# tile.net
KiCad netlist of a schematic drawn in EAGLE
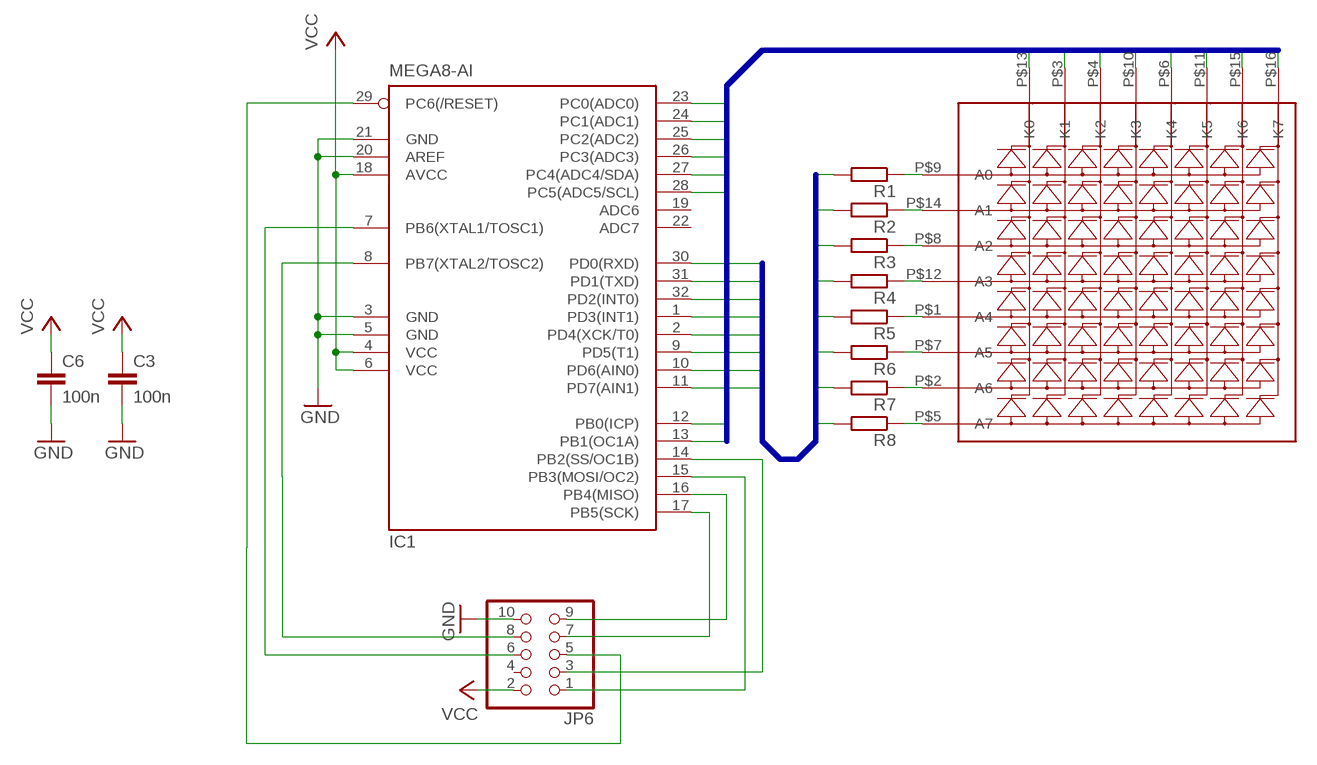
[diagram p0: schematic, sheet 1]
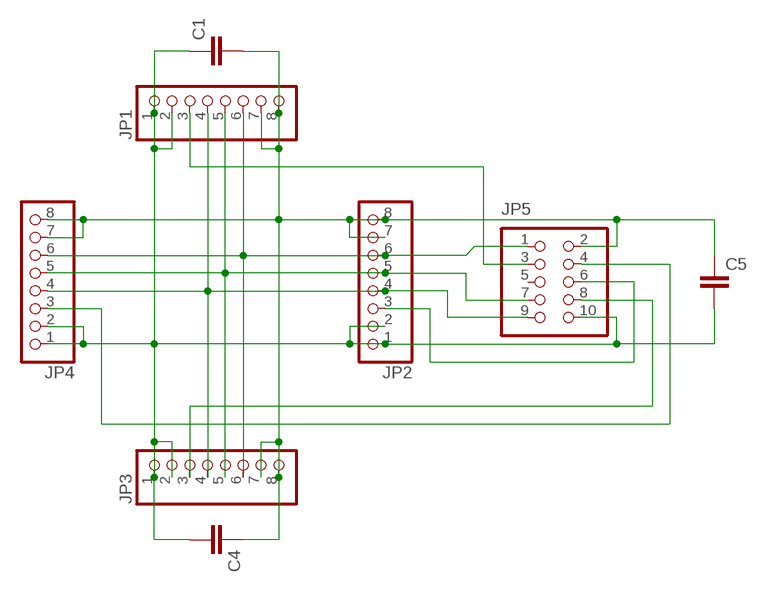
[diagram p1: schematic, sheet 2]

(export (version "E")
  (design (tool "Eeschema 10.0.6"))
  (components
    (comp (ref "C1")
      (value "C-EUC0805")
      (footprint "eagle-import:C0805")
      (libsource (lib "eagle-import") (part "C-EUC0805"))
    )
    (comp (ref "C4")
      (value "C-EUC0805")
      (footprint "eagle-import:C0805")
      (libsource (lib "eagle-import") (part "C-EUC0805"))
    )
    (comp (ref "C5")
      (value "C-EUC0805")
      (footprint "eagle-import:C0805")
      (libsource (lib "eagle-import") (part "C-EUC0805"))
    )
    (comp (ref "JP1")
      (value "PINHD-1X8_2.00")
      (footprint "eagle-import:1X08M")
      (libsource (lib "eagle-import") (part "PINHD-1X8_2.00"))
    )
    (comp (ref "JP2")
      (value "PINHD-1X8_2.00")
      (footprint "eagle-import:1X08M")
      (libsource (lib "eagle-import") (part "PINHD-1X8_2.00"))
    )
    (comp (ref "JP3")
      (value "PINHD-1X8_2.00")
      (footprint "eagle-import:1X08M")
      (libsource (lib "eagle-import") (part "PINHD-1X8_2.00"))
    )
    (comp (ref "JP4")
      (value "PINHD-1X8_2.00")
      (footprint "eagle-import:1X08M")
      (libsource (lib "eagle-import") (part "PINHD-1X8_2.00"))
    )
    (comp (ref "JP5")
      (value "PINHD-2X5_2.54")
      (footprint "eagle-import:2X05")
      (libsource (lib "eagle-import") (part "PINHD-2X5_2.54"))
    )
    (comp (ref "C3")
      (value "100n")
      (footprint "eagle-import:C0805")
      (libsource (lib "eagle-import") (part "C-EUC0805"))
    )
    (comp (ref "C6")
      (value "100n")
      (footprint "eagle-import:C0805")
      (libsource (lib "eagle-import") (part "C-EUC0805"))
    )
    (comp (ref "IC1")
      (value "MEGA8-AI")
      (footprint "eagle-import:TQFP32-08")
      (libsource (lib "eagle-import") (part "MEGA8-AI"))
    )
    (comp (ref "JP6")
      (value "PINHD-2X5_2.54")
      (footprint "eagle-import:2X05")
      (libsource (lib "eagle-import") (part "PINHD-2X5_2.54"))
    )
    (comp (ref "R1")
      (value "R-EU_M0805")
      (footprint "eagle-import:M0805")
      (libsource (lib "eagle-import") (part "R-EU_M0805"))
    )
    (comp (ref "R2")
      (value "R-EU_M0805")
      (footprint "eagle-import:M0805")
      (libsource (lib "eagle-import") (part "R-EU_M0805"))
    )
    (comp (ref "R3")
      (value "R-EU_M0805")
      (footprint "eagle-import:M0805")
      (libsource (lib "eagle-import") (part "R-EU_M0805"))
    )
    (comp (ref "R4")
      (value "R-EU_M0805")
      (footprint "eagle-import:M0805")
      (libsource (lib "eagle-import") (part "R-EU_M0805"))
    )
    (comp (ref "R5")
      (value "R-EU_M0805")
      (footprint "eagle-import:M0805")
      (libsource (lib "eagle-import") (part "R-EU_M0805"))
    )
    (comp (ref "R6")
      (value "R-EU_M0805")
      (footprint "eagle-import:M0805")
      (libsource (lib "eagle-import") (part "R-EU_M0805"))
    )
    (comp (ref "R7")
      (value "R-EU_M0805")
      (footprint "eagle-import:M0805")
      (libsource (lib "eagle-import") (part "R-EU_M0805"))
    )
    (comp (ref "R8")
      (value "R-EU_M0805")
      (footprint "eagle-import:M0805")
      (libsource (lib "eagle-import") (part "R-EU_M0805"))
    )
    (comp (ref "U$1")
      (value "LED-MATRIX")
      (footprint "eagle-import:LED-MATRIX")
      (libsource (lib "eagle-import") (part "LED-MATRIX"))
    )
  )
  (nets
    (net (code "1") (name "A0") (class "Default")
      (node (ref "IC1") (pin "30") (pinfunction "PD0(RXD)_30") (pintype "bidirectional"))
      (node (ref "R1") (pin "1") (pinfunction "1_1") (pintype "passive"))
      (node (ref "R1") (pin "2") (pinfunction "2_2") (pintype "passive"))
      (node (ref "U$1") (pin "P$9") (pinfunction "A0_P$9") (pintype "bidirectional"))
    )
    (net (code "2") (name "A1") (class "Default")
      (node (ref "IC1") (pin "31") (pinfunction "PD1(TXD)_31") (pintype "bidirectional"))
      (node (ref "R2") (pin "1") (pinfunction "1_1") (pintype "passive"))
      (node (ref "R2") (pin "2") (pinfunction "2_2") (pintype "passive"))
      (node (ref "U$1") (pin "P$14") (pinfunction "A1_P$14") (pintype "bidirectional"))
    )
    (net (code "3") (name "A2") (class "Default")
      (node (ref "IC1") (pin "32") (pinfunction "PD2(INT0)_32") (pintype "bidirectional"))
      (node (ref "R3") (pin "1") (pinfunction "1_1") (pintype "passive"))
      (node (ref "R3") (pin "2") (pinfunction "2_2") (pintype "passive"))
      (node (ref "U$1") (pin "P$8") (pinfunction "A2_P$8") (pintype "bidirectional"))
    )
    (net (code "4") (name "A3") (class "Default")
      (node (ref "IC1") (pin "1") (pinfunction "PD3(INT1)_1") (pintype "bidirectional"))
      (node (ref "R4") (pin "1") (pinfunction "1_1") (pintype "passive"))
      (node (ref "R4") (pin "2") (pinfunction "2_2") (pintype "passive"))
      (node (ref "U$1") (pin "P$12") (pinfunction "A3_P$12") (pintype "bidirectional"))
    )
    (net (code "5") (name "A4") (class "Default")
      (node (ref "IC1") (pin "2") (pinfunction "PD4(XCK/T0)_2") (pintype "bidirectional"))
      (node (ref "R5") (pin "1") (pinfunction "1_1") (pintype "passive"))
      (node (ref "U$1") (pin "P$1") (pinfunction "A4_P$1") (pintype "bidirectional"))
    )
    (net (code "6") (name "A5") (class "Default")
      (node (ref "IC1") (pin "9") (pinfunction "PD5(T1)_9") (pintype "bidirectional"))
      (node (ref "R5") (pin "2") (pinfunction "2_2") (pintype "passive"))
      (node (ref "R6") (pin "1") (pinfunction "1_1") (pintype "passive"))
      (node (ref "R6") (pin "2") (pinfunction "2_2") (pintype "passive"))
      (node (ref "U$1") (pin "P$7") (pinfunction "A5_P$7") (pintype "bidirectional"))
    )
    (net (code "7") (name "A6") (class "Default")
      (node (ref "IC1") (pin "10") (pinfunction "PD6(AIN0)_10") (pintype "bidirectional"))
      (node (ref "R7") (pin "1") (pinfunction "1_1") (pintype "passive"))
      (node (ref "R7") (pin "2") (pinfunction "2_2") (pintype "passive"))
      (node (ref "U$1") (pin "P$2") (pinfunction "A6_P$2") (pintype "bidirectional"))
    )
    (net (code "8") (name "A7") (class "Default")
      (node (ref "IC1") (pin "11") (pinfunction "PD7(AIN1)_11") (pintype "bidirectional"))
      (node (ref "R8") (pin "1") (pinfunction "1_1") (pintype "passive"))
      (node (ref "R8") (pin "2") (pinfunction "2_2") (pintype "passive"))
      (node (ref "U$1") (pin "P$5") (pinfunction "A7_P$5") (pintype "bidirectional"))
    )
    (net (code "9") (name "GND") (class "Default")
      (node (ref "C1") (pin "1") (pinfunction "1_1") (pintype "passive"))
      (node (ref "C3") (pin "2") (pinfunction "2_2") (pintype "passive"))
      (node (ref "C4") (pin "2") (pinfunction "2_2") (pintype "passive"))
      (node (ref "C5") (pin "2") (pinfunction "2_2") (pintype "passive"))
      (node (ref "C6") (pin "2") (pinfunction "2_2") (pintype "passive"))
      (node (ref "IC1") (pin "20") (pinfunction "AREF_20") (pintype "passive"))
      (node (ref "IC1") (pin "21") (pinfunction "GND_21") (pintype "power_in"))
      (node (ref "IC1") (pin "3") (pinfunction "GND_3") (pintype "power_in"))
      (node (ref "IC1") (pin "5") (pinfunction "GND_5") (pintype "power_in"))
      (node (ref "JP1") (pin "1") (pinfunction "1_1") (pintype "passive"))
      (node (ref "JP1") (pin "2") (pinfunction "2_2") (pintype "passive"))
      (node (ref "JP2") (pin "1") (pinfunction "1_1") (pintype "passive"))
      (node (ref "JP2") (pin "2") (pinfunction "2_2") (pintype "passive"))
      (node (ref "JP3") (pin "1") (pinfunction "1_1") (pintype "passive"))
      (node (ref "JP3") (pin "2") (pinfunction "2_2") (pintype "passive"))
      (node (ref "JP4") (pin "1") (pinfunction "1_1") (pintype "passive"))
      (node (ref "JP4") (pin "2") (pinfunction "2_2") (pintype "passive"))
      (node (ref "JP5") (pin "10") (pinfunction "10_10") (pintype "passive"))
      (node (ref "JP6") (pin "10") (pinfunction "10_10") (pintype "passive"))
    )
    (net (code "10") (name "K0") (class "Default")
      (node (ref "IC1") (pin "23") (pinfunction "PC0(ADC0)_23") (pintype "bidirectional"))
      (node (ref "U$1") (pin "P$13") (pinfunction "K0_P$13") (pintype "bidirectional"))
    )
    (net (code "11") (name "K1") (class "Default")
      (node (ref "IC1") (pin "24") (pinfunction "PC1(ADC1)_24") (pintype "bidirectional"))
      (node (ref "U$1") (pin "P$3") (pinfunction "K1_P$3") (pintype "bidirectional"))
    )
    (net (code "12") (name "K2") (class "Default")
      (node (ref "IC1") (pin "25") (pinfunction "PC2(ADC2)_25") (pintype "bidirectional"))
      (node (ref "U$1") (pin "P$4") (pinfunction "K2_P$4") (pintype "bidirectional"))
    )
    (net (code "13") (name "K3") (class "Default")
      (node (ref "IC1") (pin "26") (pinfunction "PC3(ADC3)_26") (pintype "bidirectional"))
      (node (ref "U$1") (pin "P$10") (pinfunction "K3_P$10") (pintype "bidirectional"))
    )
    (net (code "14") (name "K4") (class "Default")
      (node (ref "IC1") (pin "27") (pinfunction "PC4(ADC4/SDA)_27") (pintype "bidirectional"))
      (node (ref "U$1") (pin "P$6") (pinfunction "K4_P$6") (pintype "bidirectional"))
    )
    (net (code "15") (name "K5") (class "Default")
      (node (ref "IC1") (pin "28") (pinfunction "PC5(ADC5/SCL)_28") (pintype "bidirectional"))
      (node (ref "U$1") (pin "P$11") (pinfunction "K5_P$11") (pintype "bidirectional"))
    )
    (net (code "16") (name "K6") (class "Default")
      (node (ref "IC1") (pin "12") (pinfunction "PB0(ICP)_12") (pintype "bidirectional"))
      (node (ref "U$1") (pin "P$15") (pinfunction "K6_P$15") (pintype "bidirectional"))
    )
    (net (code "17") (name "K7") (class "Default")
      (node (ref "IC1") (pin "13") (pinfunction "PB1(OC1A)_13") (pintype "bidirectional"))
      (node (ref "U$1") (pin "P$16") (pinfunction "K7_P$16") (pintype "bidirectional"))
    )
    (net (code "18") (name "Net-(IC1-PB2(SS{slash}OC1B))") (class "Default")
      (node (ref "IC1") (pin "14") (pinfunction "PB2(SS/OC1B)_14") (pintype "bidirectional"))
      (node (ref "JP6") (pin "3") (pinfunction "3_3") (pintype "passive"))
    )
    (net (code "19") (name "Net-(IC1-PB3(MOSI{slash}OC2))") (class "Default")
      (node (ref "IC1") (pin "15") (pinfunction "PB3(MOSI/OC2)_15") (pintype "bidirectional"))
      (node (ref "JP6") (pin "1") (pinfunction "1_1") (pintype "passive"))
    )
    (net (code "20") (name "Net-(IC1-PB4(MISO))") (class "Default")
      (node (ref "IC1") (pin "16") (pinfunction "PB4(MISO)_16") (pintype "bidirectional"))
      (node (ref "JP6") (pin "9") (pinfunction "9_9") (pintype "passive"))
    )
    (net (code "21") (name "Net-(IC1-PB5(SCK))") (class "Default")
      (node (ref "IC1") (pin "17") (pinfunction "PB5(SCK)_17") (pintype "bidirectional"))
      (node (ref "JP6") (pin "7") (pinfunction "7_7") (pintype "passive"))
    )
    (net (code "22") (name "Net-(IC1-PB6(XTAL1{slash}TOSC1))") (class "Default")
      (node (ref "IC1") (pin "7") (pinfunction "PB6(XTAL1/TOSC1)_7") (pintype "bidirectional"))
      (node (ref "JP6") (pin "6") (pinfunction "6_6") (pintype "passive"))
    )
    (net (code "23") (name "Net-(IC1-PB7(XTAL2{slash}TOSC2))") (class "Default")
      (node (ref "IC1") (pin "8") (pinfunction "PB7(XTAL2/TOSC2)_8") (pintype "bidirectional"))
      (node (ref "JP6") (pin "8") (pinfunction "8_8") (pintype "passive"))
    )
    (net (code "24") (name "Net-(IC1-PC6({slash}RESET))") (class "Default")
      (node (ref "IC1") (pin "29") (pinfunction "PC6(/RESET)_29") (pintype "bidirectional"))
      (node (ref "JP6") (pin "5") (pinfunction "5_5") (pintype "passive"))
    )
    (net (code "25") (name "Net-(JP1-Pad3)") (class "Default")
      (node (ref "JP1") (pin "3") (pinfunction "3_3") (pintype "passive"))
      (node (ref "JP5") (pin "3") (pinfunction "3_3") (pintype "passive"))
    )
    (net (code "26") (name "Net-(JP1-Pad4)") (class "Default")
      (node (ref "JP1") (pin "4") (pinfunction "4_4") (pintype "passive"))
      (node (ref "JP2") (pin "4") (pinfunction "4_4") (pintype "passive"))
      (node (ref "JP3") (pin "4") (pinfunction "4_4") (pintype "passive"))
      (node (ref "JP4") (pin "4") (pinfunction "4_4") (pintype "passive"))
      (node (ref "JP5") (pin "9") (pinfunction "9_9") (pintype "passive"))
    )
    (net (code "27") (name "Net-(JP1-Pad5)") (class "Default")
      (node (ref "JP1") (pin "5") (pinfunction "5_5") (pintype "passive"))
      (node (ref "JP2") (pin "5") (pinfunction "5_5") (pintype "passive"))
      (node (ref "JP3") (pin "5") (pinfunction "5_5") (pintype "passive"))
      (node (ref "JP4") (pin "5") (pinfunction "5_5") (pintype "passive"))
      (node (ref "JP5") (pin "7") (pinfunction "7_7") (pintype "passive"))
    )
    (net (code "28") (name "Net-(JP1-Pad6)") (class "Default")
      (node (ref "JP1") (pin "6") (pinfunction "6_6") (pintype "passive"))
      (node (ref "JP2") (pin "6") (pinfunction "6_6") (pintype "passive"))
      (node (ref "JP3") (pin "6") (pinfunction "6_6") (pintype "passive"))
      (node (ref "JP4") (pin "6") (pinfunction "6_6") (pintype "passive"))
      (node (ref "JP5") (pin "1") (pinfunction "1_1") (pintype "passive"))
    )
    (net (code "29") (name "Net-(JP2-Pad3)") (class "Default")
      (node (ref "JP2") (pin "3") (pinfunction "3_3") (pintype "passive"))
      (node (ref "JP5") (pin "6") (pinfunction "6_6") (pintype "passive"))
    )
    (net (code "30") (name "Net-(JP3-Pad3)") (class "Default")
      (node (ref "JP3") (pin "3") (pinfunction "3_3") (pintype "passive"))
      (node (ref "JP5") (pin "8") (pinfunction "8_8") (pintype "passive"))
    )
    (net (code "31") (name "Net-(JP4-Pad3)") (class "Default")
      (node (ref "JP4") (pin "3") (pinfunction "3_3") (pintype "passive"))
      (node (ref "JP5") (pin "4") (pinfunction "4_4") (pintype "passive"))
    )
    (net (code "32") (name "VCC") (class "Default")
      (node (ref "C1") (pin "2") (pinfunction "2_2") (pintype "passive"))
      (node (ref "C3") (pin "1") (pinfunction "1_1") (pintype "passive"))
      (node (ref "C4") (pin "1") (pinfunction "1_1") (pintype "passive"))
      (node (ref "C5") (pin "1") (pinfunction "1_1") (pintype "passive"))
      (node (ref "C6") (pin "1") (pinfunction "1_1") (pintype "passive"))
      (node (ref "IC1") (pin "18") (pinfunction "AVCC_18") (pintype "power_in"))
      (node (ref "IC1") (pin "4") (pinfunction "VCC_4") (pintype "power_in"))
      (node (ref "IC1") (pin "6") (pinfunction "VCC_6") (pintype "power_in"))
      (node (ref "JP1") (pin "7") (pinfunction "7_7") (pintype "passive"))
      (node (ref "JP1") (pin "8") (pinfunction "8_8") (pintype "passive"))
      (node (ref "JP2") (pin "7") (pinfunction "7_7") (pintype "passive"))
      (node (ref "JP2") (pin "8") (pinfunction "8_8") (pintype "passive"))
      (node (ref "JP3") (pin "7") (pinfunction "7_7") (pintype "passive"))
      (node (ref "JP3") (pin "8") (pinfunction "8_8") (pintype "passive"))
      (node (ref "JP4") (pin "7") (pinfunction "7_7") (pintype "passive"))
      (node (ref "JP4") (pin "8") (pinfunction "8_8") (pintype "passive"))
      (node (ref "JP5") (pin "2") (pinfunction "2_2") (pintype "passive"))
      (node (ref "JP6") (pin "2") (pinfunction "2_2") (pintype "passive"))
    )
    (net (code "33") (name "unconnected-(IC1-ADC6-Pad19)") (class "Default")
      (node (ref "IC1") (pin "19") (pinfunction "ADC6_19") (pintype "bidirectional"))
    )
    (net (code "34") (name "unconnected-(IC1-ADC7-Pad22)") (class "Default")
      (node (ref "IC1") (pin "22") (pinfunction "ADC7_22") (pintype "bidirectional"))
    )
    (net (code "35") (name "unconnected-(JP5-Pad5)") (class "Default")
      (node (ref "JP5") (pin "5") (pinfunction "5_5") (pintype "passive"))
    )
    (net (code "36") (name "unconnected-(JP6-Pad4)") (class "Default")
      (node (ref "JP6") (pin "4") (pinfunction "4_4") (pintype "passive"))
    )
  )
)
